# Power.net
KiCad netlist of a schematic drawn in Altium Designer
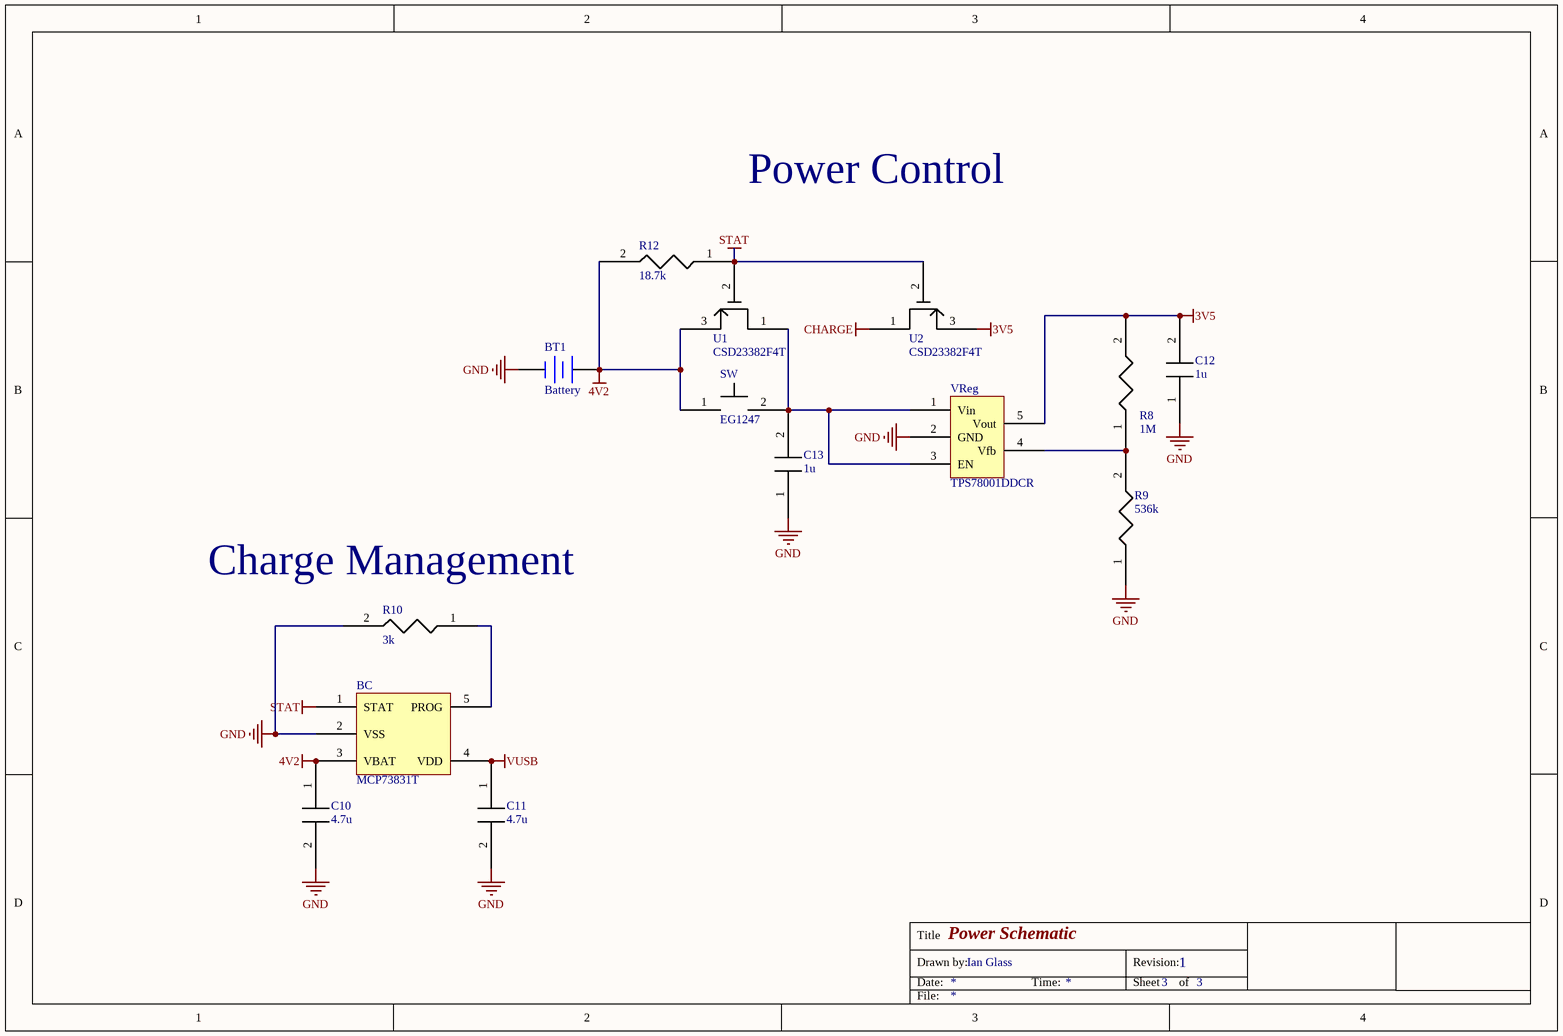
[diagram p0: Power.SchDoc]

(export (version "E")
  (design (tool "Eeschema 10.0.6"))
  (components
    (comp (ref "BC")
      (value "MCP73831T")
      (footprint "MCP73831T")
      (libsource (lib "WhereAbles") (part "MCP73831T"))
    )
    (comp (ref "BT1")
      (value "Battery")
      (footprint "BAT-2")
      (description "Multicell Battery")
      (fields (field (name "PUBLISHER") "Altium Limited"))
      (libsource (lib "Miscellaneous Devices") (part "Battery"))
    )
    (comp (ref "C10")
      (value "4.7u")
      (footprint "Capacitor 0805")
      (libsource (lib "WhereAbles") (part "Capacitor 0805"))
    )
    (comp (ref "C11")
      (value "4.7u")
      (footprint "Capacitor 0805")
      (libsource (lib "WhereAbles") (part "Capacitor 0805"))
    )
    (comp (ref "C12")
      (value "1u")
      (footprint "Capacitor 0402")
      (libsource (lib "WhereAbles") (part "Capacitor 0402"))
    )
    (comp (ref "C13")
      (value "1u")
      (footprint "Capacitor 0402")
      (libsource (lib "WhereAbles") (part "Capacitor 0402"))
    )
    (comp (ref "R8")
      (value "1M")
      (footprint "Resistor 0403")
      (libsource (lib "WhereAbles") (part "Resistor 0403"))
    )
    (comp (ref "R9")
      (value "536k")
      (footprint "Resistor 0603")
      (libsource (lib "WhereAbles") (part "Resistor 0603"))
    )
    (comp (ref "R10")
      (value "3k")
      (footprint "Resistor 0603")
      (libsource (lib "WhereAbles") (part "Resistor 0603"))
    )
    (comp (ref "R12")
      (value "18.7k")
      (footprint "Resistor 0403")
      (libsource (lib "WhereAbles") (part "Resistor 0403"))
    )
    (comp (ref "SW") (value "EG1247") (footprint "EG1247") (libsource (lib "NaviGo v3.0") (part "EG1247")))
    (comp (ref "U1")
      (value "CSD23382F4T")
      (footprint "CSD23382F4T")
      (libsource (lib "NaviGo v3.0") (part "CSD23382F4T"))
    )
    (comp (ref "U2")
      (value "CSD23382F4T")
      (footprint "CSD23382F4T")
      (libsource (lib "NaviGo v3.0") (part "CSD23382F4T"))
    )
    (comp (ref "VReg")
      (value "TPS78001DDCR")
      (footprint "TPS78001DDCR")
      (libsource (lib "WhereAbles") (part "TPS78001DDCR"))
    )
  )
  (nets
    (net (code "1") (name "3V5") (class "Default")
      (node (ref "C12") (pin "2") (pinfunction "2_2") (pintype "passive"))
      (node (ref "R8") (pin "2") (pinfunction "2_2") (pintype "passive"))
      (node (ref "U2") (pin "3") (pinfunction "3_3") (pintype "passive"))
      (node (ref "VReg") (pin "5") (pinfunction "Vout_5") (pintype "passive"))
    )
    (net (code "2") (name "4V2") (class "Default")
      (node (ref "BC") (pin "3") (pinfunction "VBAT_3") (pintype "passive"))
      (node (ref "BT1") (pin "1") (pinfunction "+_1") (pintype "passive"))
      (node (ref "C10") (pin "1") (pinfunction "1_1") (pintype "passive"))
      (node (ref "R12") (pin "2") (pinfunction "2_2") (pintype "passive"))
      (node (ref "SW") (pin "1") (pinfunction "1_1") (pintype "passive"))
      (node (ref "U1") (pin "3") (pinfunction "3_3") (pintype "passive"))
    )
    (net (code "3") (name "CHARGE") (class "Default")
      (node (ref "U2") (pin "1") (pinfunction "1_1") (pintype "passive"))
    )
    (net (code "4") (name "GND") (class "Default")
      (node (ref "BC") (pin "2") (pinfunction "VSS_2") (pintype "passive"))
      (node (ref "BT1") (pin "2") (pinfunction "-_2") (pintype "passive"))
      (node (ref "C10") (pin "2") (pinfunction "2_2") (pintype "passive"))
      (node (ref "C11") (pin "2") (pinfunction "2_2") (pintype "passive"))
      (node (ref "C12") (pin "1") (pinfunction "1_1") (pintype "passive"))
      (node (ref "C13") (pin "1") (pinfunction "1_1") (pintype "passive"))
      (node (ref "R10") (pin "2") (pinfunction "2_2") (pintype "passive"))
      (node (ref "R9") (pin "1") (pinfunction "1_1") (pintype "passive"))
      (node (ref "VReg") (pin "2") (pinfunction "GND_2") (pintype "passive"))
    )
    (net (code "5") (name "Net-(BC-PROG)") (class "Default")
      (node (ref "BC") (pin "5") (pinfunction "PROG_5") (pintype "passive"))
      (node (ref "R10") (pin "1") (pinfunction "1_1") (pintype "passive"))
    )
    (net (code "6") (name "Net-(VReg-EN)") (class "Default")
      (node (ref "C13") (pin "2") (pinfunction "2_2") (pintype "passive"))
      (node (ref "SW") (pin "2") (pinfunction "2_2") (pintype "passive"))
      (node (ref "U1") (pin "1") (pinfunction "1_1") (pintype "passive"))
      (node (ref "VReg") (pin "1") (pinfunction "Vin_1") (pintype "passive"))
      (node (ref "VReg") (pin "3") (pinfunction "EN_3") (pintype "passive"))
    )
    (net (code "7") (name "Net-(VReg-Vfb)") (class "Default")
      (node (ref "R8") (pin "1") (pinfunction "1_1") (pintype "passive"))
      (node (ref "R9") (pin "2") (pinfunction "2_2") (pintype "passive"))
      (node (ref "VReg") (pin "4") (pinfunction "Vfb_4") (pintype "passive"))
    )
    (net (code "8") (name "STAT") (class "Default")
      (node (ref "BC") (pin "1") (pinfunction "STAT_1") (pintype "passive"))
      (node (ref "R12") (pin "1") (pinfunction "1_1") (pintype "passive"))
      (node (ref "U1") (pin "2") (pinfunction "2_2") (pintype "passive"))
      (node (ref "U2") (pin "2") (pinfunction "2_2") (pintype "passive"))
    )
    (net (code "9") (name "VUSB") (class "Default")
      (node (ref "BC") (pin "4") (pinfunction "VDD_4") (pintype "passive"))
      (node (ref "C11") (pin "1") (pinfunction "1_1") (pintype "passive"))
    )
  )
)
